# OpenEVSE_PLUS_v2_5.net
KiCad netlist of a schematic drawn in EAGLE
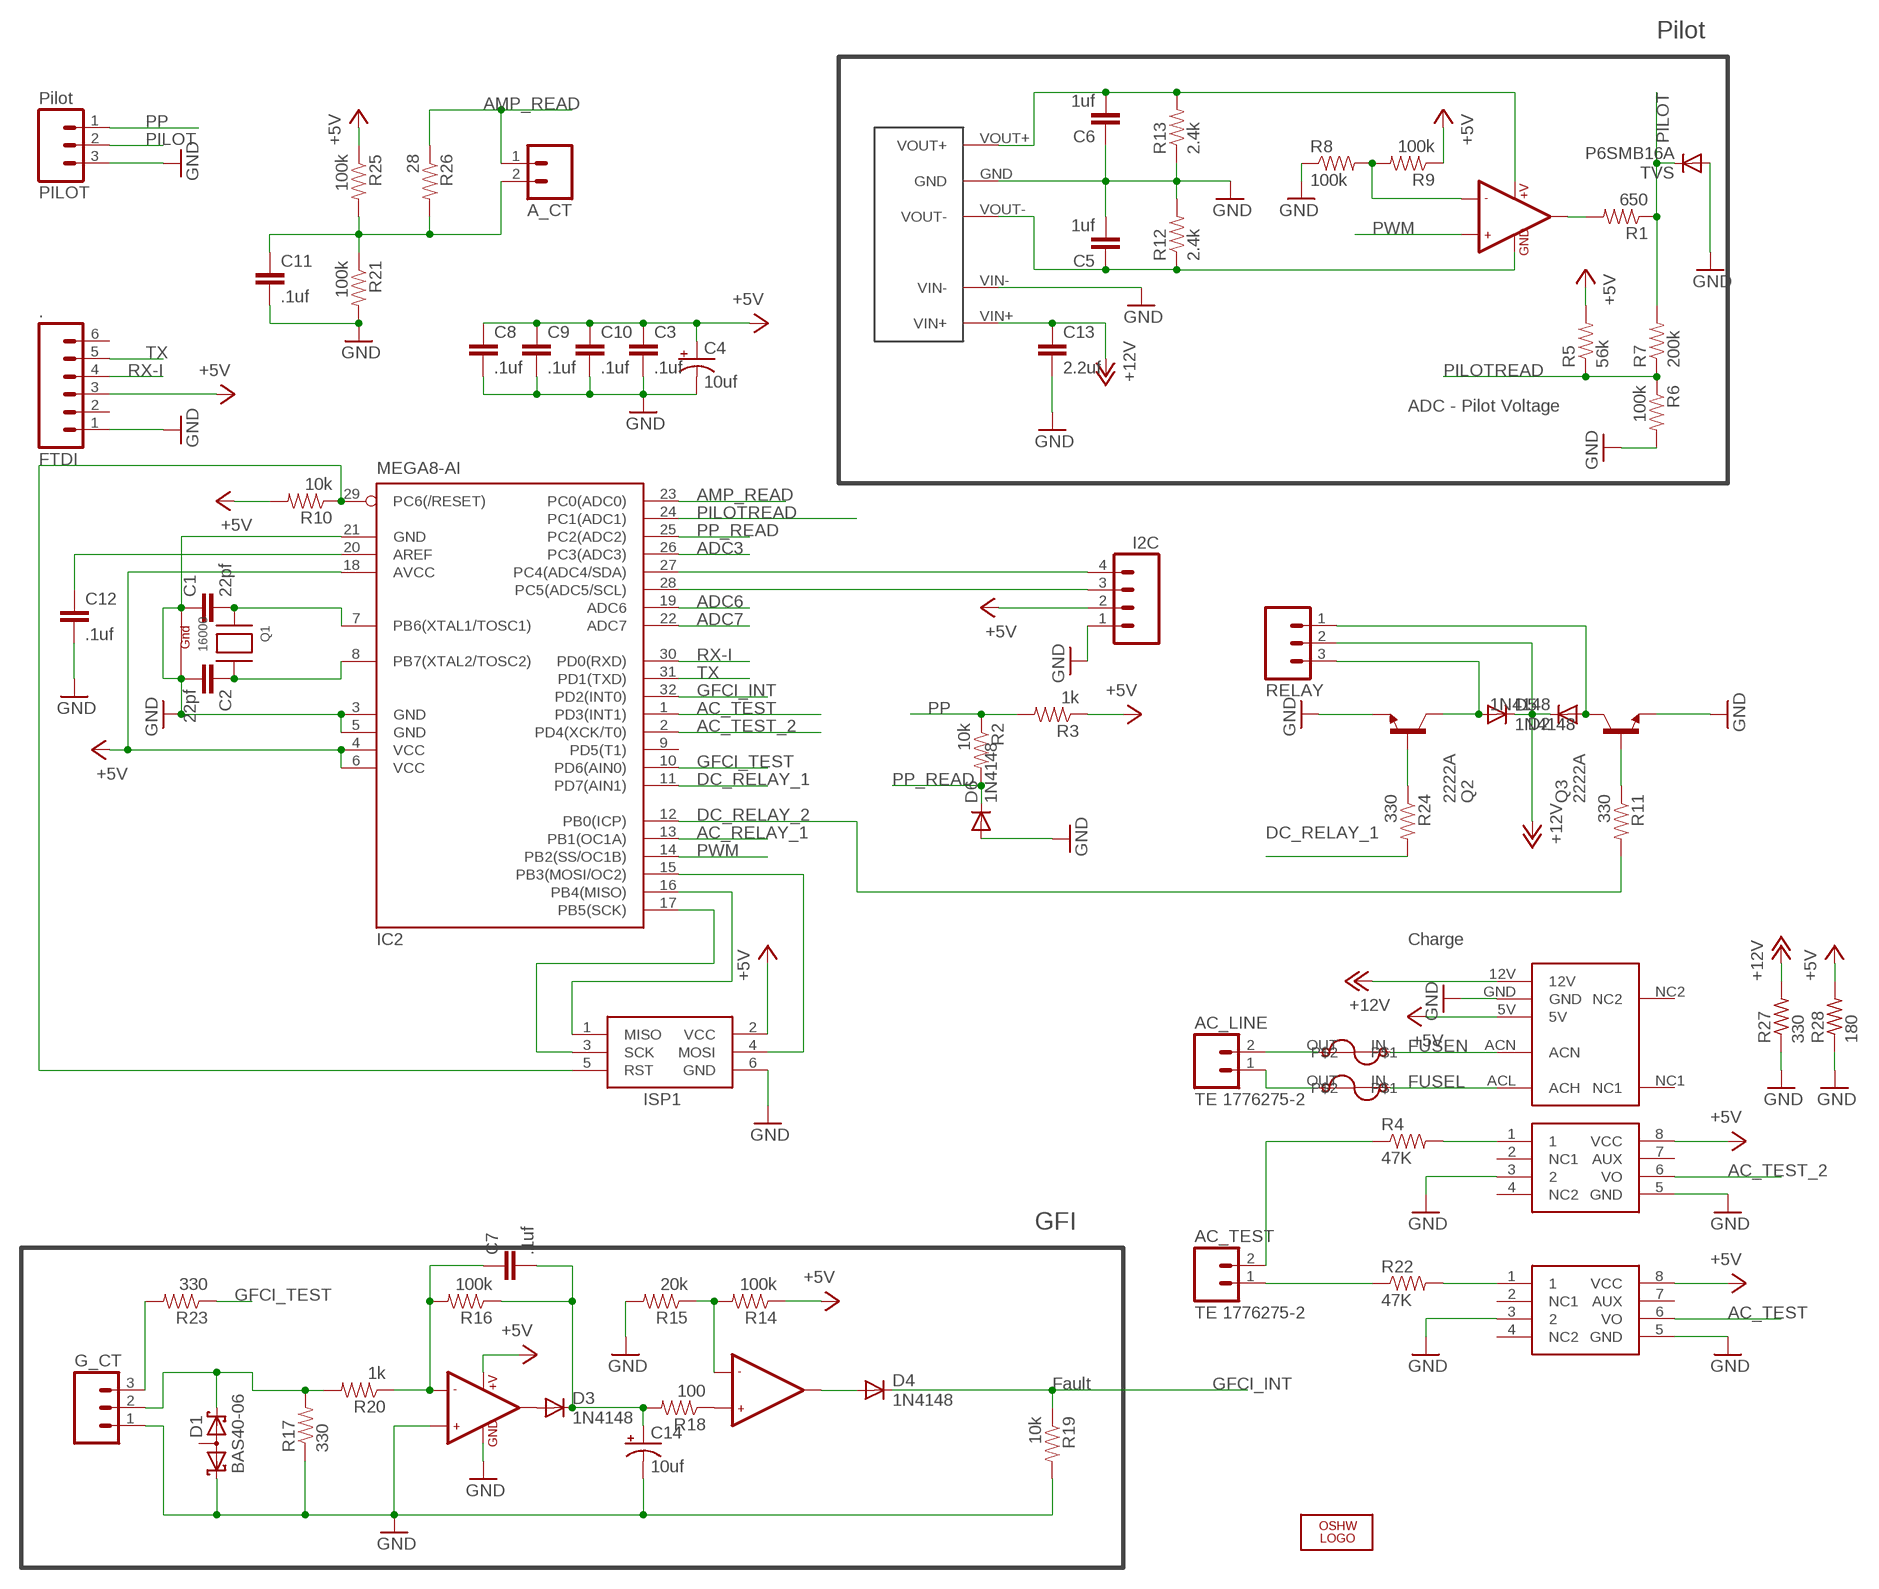
[diagram p0: schematic, sheet 1]

(export (version "E")
  (design (tool "Eeschema 10.0.6"))
  (components
    (comp (ref ".")
      (value "FTDI")
      (footprint "eagle-import:1X06_LOCK")
      (libsource (lib "eagle-import") (part "M06LOCK"))
    )
    (comp (ref "AC_LINE")
      (value "TE 1776275-2")
      (footprint "eagle-import:SCREWTERMINAL-3.5MM-2_LOCK")
      (libsource (lib "eagle-import") (part "M023.5MM_LOCK"))
    )
    (comp (ref "AC_TEST")
      (value "TE 1776275-2")
      (footprint "eagle-import:SCREWTERMINAL-3.5MM-2_LOCK")
      (libsource (lib "eagle-import") (part "M023.5MM_LOCK"))
    )
    (comp (ref "A_CT")
      (value "M02PTH")
      (footprint "eagle-import:1X02")
      (libsource (lib "eagle-import") (part "M02PTH"))
    )
    (comp (ref "C1")
      (value "22pf")
      (footprint "eagle-import:0805")
      (libsource (lib "eagle-import") (part "CAP0805"))
    )
    (comp (ref "C2")
      (value "22pf")
      (footprint "eagle-import:0805")
      (libsource (lib "eagle-import") (part "CAP0805"))
    )
    (comp (ref "C3")
      (value ".1uf")
      (footprint "eagle-import:0805")
      (libsource (lib "eagle-import") (part "CAP0805"))
    )
    (comp (ref "C4")
      (value "10uf")
      (footprint "eagle-import:EIA3216")
      (libsource (lib "eagle-import") (part "CAP_POL1206"))
    )
    (comp (ref "C5")
      (value "1uf")
      (footprint "eagle-import:0805")
      (libsource (lib "eagle-import") (part "CAP0805"))
    )
    (comp (ref "C6")
      (value "1uf")
      (footprint "eagle-import:0805")
      (libsource (lib "eagle-import") (part "CAP0805"))
    )
    (comp (ref "C7")
      (value ".1uf")
      (footprint "eagle-import:0805")
      (libsource (lib "eagle-import") (part "CAP0805"))
    )
    (comp (ref "C8")
      (value ".1uf")
      (footprint "eagle-import:0805")
      (libsource (lib "eagle-import") (part "CAP0805"))
    )
    (comp (ref "C9")
      (value ".1uf")
      (footprint "eagle-import:0805")
      (libsource (lib "eagle-import") (part "CAP0805"))
    )
    (comp (ref "C10")
      (value ".1uf")
      (footprint "eagle-import:0805")
      (libsource (lib "eagle-import") (part "CAP0805"))
    )
    (comp (ref "C11")
      (value ".1uf")
      (footprint "eagle-import:0805")
      (libsource (lib "eagle-import") (part "CAP0805"))
    )
    (comp (ref "C12")
      (value ".1uf")
      (footprint "eagle-import:0805")
      (libsource (lib "eagle-import") (part "CAP0805"))
    )
    (comp (ref "C13")
      (value "2.2uf")
      (footprint "eagle-import:0805")
      (libsource (lib "eagle-import") (part "CAP0805"))
    )
    (comp (ref "C14")
      (value "10uf")
      (footprint "eagle-import:EIA3216")
      (libsource (lib "eagle-import") (part "CAP_POL1206"))
    )
    (comp (ref "D1")
      (value "BAS40-06")
      (footprint "eagle-import:SOT23")
      (libsource (lib "eagle-import") (part "BAS40-06"))
    )
    (comp (ref "D2")
      (value "1N4148")
      (footprint "eagle-import:SOD123")
      (libsource (lib "eagle-import") (part "DIODE-SOD123"))
    )
    (comp (ref "D3")
      (value "1N4148")
      (footprint "eagle-import:SOD123")
      (libsource (lib "eagle-import") (part "DIODE-SOD123"))
    )
    (comp (ref "D4")
      (value "1N4148")
      (footprint "eagle-import:SOD123")
      (libsource (lib "eagle-import") (part "DIODE-SOD123"))
    )
    (comp (ref "D5")
      (value "1N4148")
      (footprint "eagle-import:SOD123")
      (libsource (lib "eagle-import") (part "DIODE-SOD123"))
    )
    (comp (ref "D6")
      (value "1N4148")
      (footprint "eagle-import:SOD123")
      (libsource (lib "eagle-import") (part "DIODE-SOD123"))
    )
    (comp (ref "DCDC")
      (value "D107E")
      (footprint "eagle-import:DCDC_SIP")
      (libsource (lib "eagle-import") (part "DCDC_SIP"))
    )
    (comp (ref "F1")
      (value "BEL1AFUSE")
      (footprint "eagle-import:BELFUSE1A")
      (libsource (lib "eagle-import") (part "BEL1AFUSE"))
    )
    (comp (ref "F2")
      (value "BEL1AFUSE")
      (footprint "eagle-import:BELFUSE1A")
      (libsource (lib "eagle-import") (part "BEL1AFUSE"))
    )
    (comp (ref "G_CT")
      (value "M03LOCK")
      (footprint "eagle-import:1X03_LOCK")
      (libsource (lib "eagle-import") (part "M03LOCK"))
    )
    (comp (ref "I2C")
      (value "M04LOCK")
      (footprint "eagle-import:1X04_LOCK")
      (libsource (lib "eagle-import") (part "M04LOCK"))
    )
    (comp (ref "IC1")
      (value "MID400")
      (footprint "eagle-import:DIP08")
      (libsource (lib "eagle-import") (part "MID400"))
    )
    (comp (ref "IC2")
      (value "MEGA8-AI")
      (footprint "eagle-import:TQFP32-08")
      (fields (field (name "MPN") "ATMEGA8-16AU"))
      (libsource (lib "eagle-import") (part "MEGA8-AI"))
    )
    (comp (ref "IC3")
      (value "LMV358")
      (footprint "eagle-import:SO08")
      (libsource (lib "eagle-import") (part "LMV358"))
    )
    (comp (ref "IC4")
      (value "LMV358")
      (footprint "eagle-import:SO08")
      (libsource (lib "eagle-import") (part "LMV358"))
    )
    (comp (ref "IC6")
      (value "MID400")
      (footprint "eagle-import:DIP08")
      (libsource (lib "eagle-import") (part "MID400"))
    )
    (comp (ref "ISP1")
      (value "AVRISP-6")
      (footprint "eagle-import:AVRISP")
      (libsource (lib "eagle-import") (part "AVRISP-6"))
    )
    (comp (ref "LOGO1")
      (value "OSHW_LOGO_8MILX0150-NT")
      (footprint "eagle-import:OSHW_8X150_NOTEXT")
      (libsource (lib "eagle-import") (part "OSHW_LOGO_8MILX0150-NT"))
    )
    (comp (ref "PILOT")
      (value "Pilot")
      (footprint "eagle-import:SCREWTERMINAL-3.5MM-3_LOCK.007S")
      (libsource (lib "eagle-import") (part "M03SCREW_LOCK"))
    )
    (comp (ref "Q1")
      (value "16000")
      (footprint "eagle-import:NX3225")
      (libsource (lib "eagle-import") (part "XTAL-4-3225"))
    )
    (comp (ref "Q2")
      (value "2222A")
      (footprint "eagle-import:SOT23")
      (libsource (lib "eagle-import") (part "BCX70SMD"))
    )
    (comp (ref "Q3")
      (value "2222A")
      (footprint "eagle-import:SOT23")
      (libsource (lib "eagle-import") (part "BCX70SMD"))
    )
    (comp (ref "R1")
      (value "650")
      (footprint "eagle-import:0805")
      (libsource (lib "eagle-import") (part "RESISTOR0805-RES"))
    )
    (comp (ref "R2")
      (value "10k")
      (footprint "eagle-import:0805")
      (libsource (lib "eagle-import") (part "RESISTOR0805-RES"))
    )
    (comp (ref "R3")
      (value "1k")
      (footprint "eagle-import:0805")
      (libsource (lib "eagle-import") (part "RESISTOR0805-RES"))
    )
    (comp (ref "R4")
      (value "47K")
      (footprint "eagle-import:AXIAL-0.4")
      (libsource (lib "eagle-import") (part "RESISTORPTH-1/4W"))
    )
    (comp (ref "R5")
      (value "56k")
      (footprint "eagle-import:0805")
      (libsource (lib "eagle-import") (part "RESISTOR0805-RES"))
    )
    (comp (ref "R6")
      (value "100k")
      (footprint "eagle-import:0805")
      (libsource (lib "eagle-import") (part "RESISTOR0805-RES"))
    )
    (comp (ref "R7")
      (value "200k")
      (footprint "eagle-import:0805")
      (libsource (lib "eagle-import") (part "RESISTOR0805-RES"))
    )
    (comp (ref "R8")
      (value "100k")
      (footprint "eagle-import:0805")
      (libsource (lib "eagle-import") (part "RESISTOR0805-RES"))
    )
    (comp (ref "R9")
      (value "100k")
      (footprint "eagle-import:0805")
      (libsource (lib "eagle-import") (part "RESISTOR0805-RES"))
    )
    (comp (ref "R10")
      (value "10k")
      (footprint "eagle-import:0805")
      (libsource (lib "eagle-import") (part "RESISTOR0805-RES"))
    )
    (comp (ref "R11")
      (value "330")
      (footprint "eagle-import:0805")
      (libsource (lib "eagle-import") (part "RESISTOR0805-RES"))
    )
    (comp (ref "R12")
      (value "2.4k")
      (footprint "eagle-import:0805")
      (libsource (lib "eagle-import") (part "RESISTOR0805-RES"))
    )
    (comp (ref "R13")
      (value "2.4k")
      (footprint "eagle-import:0805")
      (libsource (lib "eagle-import") (part "RESISTOR0805-RES"))
    )
    (comp (ref "R14")
      (value "100k")
      (footprint "eagle-import:0805")
      (libsource (lib "eagle-import") (part "RESISTOR0805-RES"))
    )
    (comp (ref "R15")
      (value "20k")
      (footprint "eagle-import:0805")
      (libsource (lib "eagle-import") (part "RESISTOR0805-RES"))
    )
    (comp (ref "R16")
      (value "100k")
      (footprint "eagle-import:0805")
      (libsource (lib "eagle-import") (part "RESISTOR0805-RES"))
    )
    (comp (ref "R17")
      (value "330")
      (footprint "eagle-import:0805")
      (libsource (lib "eagle-import") (part "RESISTOR0805-RES"))
    )
    (comp (ref "R18")
      (value "100")
      (footprint "eagle-import:0805")
      (libsource (lib "eagle-import") (part "RESISTOR0805-RES"))
    )
    (comp (ref "R19")
      (value "10k")
      (footprint "eagle-import:0805")
      (libsource (lib "eagle-import") (part "RESISTOR0805-RES"))
    )
    (comp (ref "R20")
      (value "1k")
      (footprint "eagle-import:0805")
      (libsource (lib "eagle-import") (part "RESISTOR0805-RES"))
    )
    (comp (ref "R21")
      (value "100k")
      (footprint "eagle-import:0805")
      (libsource (lib "eagle-import") (part "RESISTOR0805-RES"))
    )
    (comp (ref "R22")
      (value "47K")
      (footprint "eagle-import:AXIAL-0.4")
      (libsource (lib "eagle-import") (part "RESISTORPTH-1/4W"))
    )
    (comp (ref "R23")
      (value "330")
      (footprint "eagle-import:0805")
      (libsource (lib "eagle-import") (part "RESISTOR0805-RES"))
    )
    (comp (ref "R24")
      (value "330")
      (footprint "eagle-import:0805")
      (libsource (lib "eagle-import") (part "RESISTOR0805-RES"))
    )
    (comp (ref "R25")
      (value "100k")
      (footprint "eagle-import:0805")
      (libsource (lib "eagle-import") (part "RESISTOR0805-RES"))
    )
    (comp (ref "R26")
      (value "28")
      (footprint "eagle-import:0805")
      (libsource (lib "eagle-import") (part "RESISTOR0805-RES"))
    )
    (comp (ref "R27")
      (value "330")
      (footprint "eagle-import:R1206")
      (libsource (lib "eagle-import") (part "R-US_R1206"))
    )
    (comp (ref "R28")
      (value "180")
      (footprint "eagle-import:R1206")
      (libsource (lib "eagle-import") (part "R-US_R1206"))
    )
    (comp (ref "RELAY")
      (value "M03SCREW_LOCK")
      (footprint "eagle-import:SCREWTERMINAL-3.5MM-3_LOCK.007S")
      (libsource (lib "eagle-import") (part "M03SCREW_LOCK"))
    )
    (comp (ref "TVS")
      (value "P6SMB16A")
      (footprint "eagle-import:SMB")
      (libsource (lib "eagle-import") (part "DIODE-SMB"))
    )
    (comp (ref "U$1")
      (value "MPM-04E-1205")
      (footprint "eagle-import:MPM-04E-1205")
      (libsource (lib "eagle-import") (part "MPM-04E-1205"))
    )
  )
  (nets
    (net (code "1") (name "+5V") (class "Default")
      (node (ref ".") (pin "3") (pinfunction "3_3") (pintype "passive"))
      (node (ref "C10") (pin "1") (pinfunction "1_1") (pintype "passive"))
      (node (ref "C3") (pin "1") (pinfunction "1_1") (pintype "passive"))
      (node (ref "C4") (pin "A") (pinfunction "+_A") (pintype "passive"))
      (node (ref "C8") (pin "1") (pinfunction "1_1") (pintype "passive"))
      (node (ref "C9") (pin "1") (pinfunction "1_1") (pintype "passive"))
      (node (ref "I2C") (pin "2") (pinfunction "2_2") (pintype "passive"))
      (node (ref "IC1") (pin "8") (pinfunction "VCC_8") (pintype "bidirectional"))
      (node (ref "IC2") (pin "18") (pinfunction "AVCC_18") (pintype "power_in"))
      (node (ref "IC2") (pin "4") (pinfunction "VCC_4") (pintype "power_in"))
      (node (ref "IC2") (pin "6") (pinfunction "VCC_6") (pintype "power_in"))
      (node (ref "IC3") (pin "8") (pinfunction "+V_8") (pintype "power_in"))
      (node (ref "IC6") (pin "8") (pinfunction "VCC_8") (pintype "bidirectional"))
      (node (ref "ISP1") (pin "2") (pinfunction "VCC_2") (pintype "power_in"))
      (node (ref "R10") (pin "2") (pinfunction "2_2") (pintype "passive"))
      (node (ref "R14") (pin "1") (pinfunction "1_1") (pintype "passive"))
      (node (ref "R25") (pin "1") (pinfunction "1_1") (pintype "passive"))
      (node (ref "R28") (pin "2") (pinfunction "2_2") (pintype "passive"))
      (node (ref "R3") (pin "1") (pinfunction "1_1") (pintype "passive"))
      (node (ref "R5") (pin "2") (pinfunction "2_2") (pintype "passive"))
      (node (ref "R9") (pin "1") (pinfunction "1_1") (pintype "passive"))
      (node (ref "U$1") (pin "5V") (pinfunction "5V_5V") (pintype "bidirectional"))
    )
    (net (code "2") (name "+12V") (class "Default")
      (node (ref "C13") (pin "1") (pinfunction "1_1") (pintype "passive"))
      (node (ref "D2") (pin "C") (pinfunction "C_C") (pintype "passive"))
      (node (ref "D5") (pin "C") (pinfunction "C_C") (pintype "passive"))
      (node (ref "DCDC") (pin "VIN+") (pinfunction "VIN+_VIN+") (pintype "bidirectional"))
      (node (ref "R27") (pin "2") (pinfunction "2_2") (pintype "passive"))
      (node (ref "RELAY") (pin "2") (pinfunction "2_2") (pintype "passive"))
      (node (ref "U$1") (pin "12V") (pinfunction "12V_12V") (pintype "bidirectional"))
    )
    (net (code "3") (name "/AC_RELAY_1") (class "Default")
      (node (ref "IC2") (pin "13") (pinfunction "PB1(OC1A)_13") (pintype "bidirectional"))
    )
    (net (code "4") (name "/AC_TEST") (class "Default")
      (node (ref "IC2") (pin "1") (pinfunction "PD3(INT1)_1") (pintype "bidirectional"))
      (node (ref "IC6") (pin "6") (pinfunction "VO_6") (pintype "bidirectional"))
    )
    (net (code "5") (name "/AC_TEST_2") (class "Default")
      (node (ref "IC1") (pin "6") (pinfunction "VO_6") (pintype "bidirectional"))
      (node (ref "IC2") (pin "2") (pinfunction "PD4(XCK/T0)_2") (pintype "bidirectional"))
    )
    (net (code "6") (name "/ADC3") (class "Default")
      (node (ref "IC2") (pin "26") (pinfunction "PC3(ADC3)_26") (pintype "bidirectional"))
    )
    (net (code "7") (name "/ADC6") (class "Default")
      (node (ref "IC2") (pin "19") (pinfunction "ADC6_19") (pintype "bidirectional"))
    )
    (net (code "8") (name "/ADC7") (class "Default")
      (node (ref "IC2") (pin "22") (pinfunction "ADC7_22") (pintype "bidirectional"))
    )
    (net (code "9") (name "/AMP_READ") (class "Default")
      (node (ref "A_CT") (pin "1") (pinfunction "1_1") (pintype "passive"))
      (node (ref "IC2") (pin "23") (pinfunction "PC0(ADC0)_23") (pintype "bidirectional"))
      (node (ref "R26") (pin "1") (pinfunction "1_1") (pintype "passive"))
    )
    (net (code "10") (name "/DC_RELAY_1") (class "Default")
      (node (ref "IC2") (pin "11") (pinfunction "PD7(AIN1)_11") (pintype "bidirectional"))
      (node (ref "R24") (pin "2") (pinfunction "2_2") (pintype "passive"))
    )
    (net (code "11") (name "/DC_RELAY_2") (class "Default")
      (node (ref "IC2") (pin "12") (pinfunction "PB0(ICP)_12") (pintype "bidirectional"))
      (node (ref "R11") (pin "2") (pinfunction "2_2") (pintype "passive"))
    )
    (net (code "12") (name "/FUSEL") (class "Default")
      (node (ref "F2") (pin "IN") (pinfunction "P$2_IN") (pintype "bidirectional"))
      (node (ref "U$1") (pin "ACL") (pinfunction "ACH_ACL") (pintype "bidirectional"))
    )
    (net (code "13") (name "/FUSEN") (class "Default")
      (node (ref "F1") (pin "IN") (pinfunction "P$2_IN") (pintype "bidirectional"))
      (node (ref "U$1") (pin "ACN") (pinfunction "ACN_ACN") (pintype "bidirectional"))
    )
    (net (code "14") (name "/GFCI_INT") (class "Default")
      (node (ref "D4") (pin "C") (pinfunction "C_C") (pintype "passive"))
      (node (ref "IC2") (pin "32") (pinfunction "PD2(INT0)_32") (pintype "bidirectional"))
      (node (ref "R19") (pin "1") (pinfunction "1_1") (pintype "passive"))
    )
    (net (code "15") (name "/GFCI_TEST") (class "Default")
      (node (ref "IC2") (pin "10") (pinfunction "PD6(AIN0)_10") (pintype "bidirectional"))
      (node (ref "R23") (pin "1") (pinfunction "1_1") (pintype "passive"))
    )
    (net (code "16") (name "/PILOT") (class "Default")
      (node (ref "PILOT") (pin "2") (pinfunction "2_2") (pintype "passive"))
      (node (ref "R1") (pin "1") (pinfunction "1_1") (pintype "passive"))
      (node (ref "R7") (pin "2") (pinfunction "2_2") (pintype "passive"))
      (node (ref "TVS") (pin "C") (pinfunction "C_C") (pintype "passive"))
    )
    (net (code "17") (name "/PILOTREAD") (class "Default")
      (node (ref "IC2") (pin "24") (pinfunction "PC1(ADC1)_24") (pintype "bidirectional"))
      (node (ref "R5") (pin "1") (pinfunction "1_1") (pintype "passive"))
      (node (ref "R6") (pin "1") (pinfunction "1_1") (pintype "passive"))
      (node (ref "R7") (pin "1") (pinfunction "1_1") (pintype "passive"))
    )
    (net (code "18") (name "/PP") (class "Default")
      (node (ref "PILOT") (pin "1") (pinfunction "1_1") (pintype "passive"))
      (node (ref "R2") (pin "1") (pinfunction "1_1") (pintype "passive"))
      (node (ref "R3") (pin "2") (pinfunction "2_2") (pintype "passive"))
    )
    (net (code "19") (name "/PP_READ") (class "Default")
      (node (ref "D6") (pin "C") (pinfunction "C_C") (pintype "passive"))
      (node (ref "IC2") (pin "25") (pinfunction "PC2(ADC2)_25") (pintype "bidirectional"))
      (node (ref "R2") (pin "2") (pinfunction "2_2") (pintype "passive"))
    )
    (net (code "20") (name "/PWM") (class "Default")
      (node (ref "IC2") (pin "14") (pinfunction "PB2(SS/OC1B)_14") (pintype "bidirectional"))
      (node (ref "IC4") (pin "3") (pinfunction "+IN1_3") (pintype "input"))
    )
    (net (code "21") (name "/RX-I") (class "Default")
      (node (ref ".") (pin "4") (pinfunction "4_4") (pintype "passive"))
      (node (ref "IC2") (pin "30") (pinfunction "PD0(RXD)_30") (pintype "bidirectional"))
    )
    (net (code "22") (name "/TX") (class "Default")
      (node (ref ".") (pin "5") (pinfunction "5_5") (pintype "passive"))
      (node (ref "IC2") (pin "31") (pinfunction "PD1(TXD)_31") (pintype "bidirectional"))
    )
    (net (code "23") (name "GND") (class "Default")
      (node (ref ".") (pin "1") (pinfunction "1_1") (pintype "passive"))
      (node (ref "C1") (pin "1") (pinfunction "1_1") (pintype "passive"))
      (node (ref "C10") (pin "2") (pinfunction "2_2") (pintype "passive"))
      (node (ref "C11") (pin "2") (pinfunction "2_2") (pintype "passive"))
      (node (ref "C12") (pin "2") (pinfunction "2_2") (pintype "passive"))
      (node (ref "C13") (pin "2") (pinfunction "2_2") (pintype "passive"))
      (node (ref "C14") (pin "C") (pinfunction "-_C") (pintype "passive"))
      (node (ref "C2") (pin "2") (pinfunction "2_2") (pintype "passive"))
      (node (ref "C3") (pin "2") (pinfunction "2_2") (pintype "passive"))
      (node (ref "C4") (pin "C") (pinfunction "-_C") (pintype "passive"))
      (node (ref "C5") (pin "2") (pinfunction "2_2") (pintype "passive"))
      (node (ref "C6") (pin "1") (pinfunction "1_1") (pintype "passive"))
      (node (ref "C8") (pin "2") (pinfunction "2_2") (pintype "passive"))
      (node (ref "C9") (pin "2") (pinfunction "2_2") (pintype "passive"))
      (node (ref "D1") (pin "1") (pinfunction "K1_1") (pintype "passive"))
      (node (ref "D6") (pin "A") (pinfunction "A_A") (pintype "passive"))
      (node (ref "DCDC") (pin "GND") (pinfunction "GND_GND") (pintype "bidirectional"))
      (node (ref "DCDC") (pin "VIN-") (pinfunction "VIN-_VIN-") (pintype "bidirectional"))
      (node (ref "G_CT") (pin "1") (pinfunction "1_1") (pintype "passive"))
      (node (ref "I2C") (pin "1") (pinfunction "1_1") (pintype "passive"))
      (node (ref "IC1") (pin "3") (pinfunction "2_3") (pintype "bidirectional"))
      (node (ref "IC1") (pin "5") (pinfunction "GND_5") (pintype "bidirectional"))
      (node (ref "IC2") (pin "21") (pinfunction "GND_21") (pintype "power_in"))
      (node (ref "IC2") (pin "3") (pinfunction "GND_3") (pintype "power_in"))
      (node (ref "IC2") (pin "5") (pinfunction "GND_5") (pintype "power_in"))
      (node (ref "IC3") (pin "3") (pinfunction "+IN1_3") (pintype "input"))
      (node (ref "IC3") (pin "4") (pinfunction "GND_4") (pintype "power_in"))
      (node (ref "IC6") (pin "3") (pinfunction "2_3") (pintype "bidirectional"))
      (node (ref "IC6") (pin "5") (pinfunction "GND_5") (pintype "bidirectional"))
      (node (ref "ISP1") (pin "6") (pinfunction "GND_6") (pintype "power_in"))
      (node (ref "PILOT") (pin "3") (pinfunction "3_3") (pintype "passive"))
      (node (ref "Q1") (pin "1") (pinfunction "G1_1") (pintype "power_in"))
      (node (ref "Q1") (pin "3") (pinfunction "G2_3") (pintype "power_in"))
      (node (ref "Q2") (pin "2") (pinfunction "E_2") (pintype "passive"))
      (node (ref "Q3") (pin "2") (pinfunction "E_2") (pintype "passive"))
      (node (ref "R12") (pin "2") (pinfunction "2_2") (pintype "passive"))
      (node (ref "R13") (pin "1") (pinfunction "1_1") (pintype "passive"))
      (node (ref "R15") (pin "2") (pinfunction "2_2") (pintype "passive"))
      (node (ref "R17") (pin "1") (pinfunction "1_1") (pintype "passive"))
      (node (ref "R19") (pin "2") (pinfunction "2_2") (pintype "passive"))
      (node (ref "R21") (pin "2") (pinfunction "2_2") (pintype "passive"))
      (node (ref "R27") (pin "1") (pinfunction "1_1") (pintype "passive"))
      (node (ref "R28") (pin "1") (pinfunction "1_1") (pintype "passive"))
      (node (ref "R6") (pin "2") (pinfunction "2_2") (pintype "passive"))
      (node (ref "R8") (pin "1") (pinfunction "1_1") (pintype "passive"))
      (node (ref "TVS") (pin "A") (pinfunction "A_A") (pintype "passive"))
      (node (ref "U$1") (pin "GND") (pinfunction "GND_GND") (pintype "bidirectional"))
    )
    (net (code "24") (name "Net-(A_CT-Pad2)") (class "Default")
      (node (ref "A_CT") (pin "2") (pinfunction "2_2") (pintype "passive"))
      (node (ref "C11") (pin "1") (pinfunction "1_1") (pintype "passive"))
      (node (ref "R21") (pin "1") (pinfunction "1_1") (pintype "passive"))
      (node (ref "R25") (pin "2") (pinfunction "2_2") (pintype "passive"))
      (node (ref "R26") (pin "2") (pinfunction "2_2") (pintype "passive"))
    )
    (net (code "25") (name "Net-(C14-+)") (class "Default")
      (node (ref "C14") (pin "A") (pinfunction "+_A") (pintype "passive"))
      (node (ref "C7") (pin "2") (pinfunction "2_2") (pintype "passive"))
      (node (ref "D3") (pin "C") (pinfunction "C_C") (pintype "passive"))
      (node (ref "R16") (pin "1") (pinfunction "1_1") (pintype "passive"))
      (node (ref "R18") (pin "2") (pinfunction "2_2") (pintype "passive"))
    )
    (net (code "26") (name "Net-(D1-K2)") (class "Default")
      (node (ref "D1") (pin "2") (pinfunction "K2_2") (pintype "passive"))
      (node (ref "G_CT") (pin "2") (pinfunction "2_2") (pintype "passive"))
      (node (ref "R17") (pin "2") (pinfunction "2_2") (pintype "passive"))
      (node (ref "R20") (pin "2") (pinfunction "2_2") (pintype "passive"))
    )
    (net (code "27") (name "Net-(F1-P$1)") (class "Default")
      (node (ref "AC_LINE") (pin "2") (pinfunction "2_2") (pintype "passive"))
      (node (ref "F1") (pin "OUT") (pinfunction "P$1_OUT") (pintype "bidirectional"))
    )
    (net (code "28") (name "Net-(F2-P$1)") (class "Default")
      (node (ref "AC_LINE") (pin "1") (pinfunction "1_1") (pintype "passive"))
      (node (ref "F2") (pin "OUT") (pinfunction "P$1_OUT") (pintype "bidirectional"))
    )
    (net (code "29") (name "Net-(G_CT-Pad3)") (class "Default")
      (node (ref "G_CT") (pin "3") (pinfunction "3_3") (pintype "passive"))
      (node (ref "R23") (pin "2") (pinfunction "2_2") (pintype "passive"))
    )
    (net (code "30") (name "Net-(IC2-AREF)") (class "Default")
      (node (ref "C12") (pin "1") (pinfunction "1_1") (pintype "passive"))
      (node (ref "IC2") (pin "20") (pinfunction "AREF_20") (pintype "passive"))
    )
    (net (code "31") (name "Net-(IC2-PB3(MOSI{slash}OC2))") (class "Default")
      (node (ref "IC2") (pin "15") (pinfunction "PB3(MOSI/OC2)_15") (pintype "bidirectional"))
      (node (ref "ISP1") (pin "4") (pinfunction "MOSI_4") (pintype "output"))
    )
    (net (code "32") (name "Net-(IC2-PB4(MISO))") (class "Default")
      (node (ref "IC2") (pin "16") (pinfunction "PB4(MISO)_16") (pintype "bidirectional"))
      (node (ref "ISP1") (pin "1") (pinfunction "MISO_1") (pintype "input"))
    )
    (net (code "33") (name "Net-(IC2-PB5(SCK))") (class "Default")
      (node (ref "IC2") (pin "17") (pinfunction "PB5(SCK)_17") (pintype "bidirectional"))
      (node (ref "ISP1") (pin "3") (pinfunction "SCK_3") (pintype "output"))
    )
    (net (code "34") (name "Net-(IC2-PB6(XTAL1{slash}TOSC1))") (class "Default")
      (node (ref "C1") (pin "2") (pinfunction "2_2") (pintype "passive"))
      (node (ref "IC2") (pin "7") (pinfunction "PB6(XTAL1/TOSC1)_7") (pintype "bidirectional"))
      (node (ref "Q1") (pin "2") (pinfunction "X1_2") (pintype "bidirectional"))
    )
    (net (code "35") (name "Net-(IC2-PB7(XTAL2{slash}TOSC2))") (class "Default")
      (node (ref "C2") (pin "1") (pinfunction "1_1") (pintype "passive"))
      (node (ref "IC2") (pin "8") (pinfunction "PB7(XTAL2/TOSC2)_8") (pintype "bidirectional"))
      (node (ref "Q1") (pin "4") (pinfunction "X2_4") (pintype "bidirectional"))
    )
    (net (code "36") (name "Net-(IC2-PC4(ADC4{slash}SDA))") (class "Default")
      (node (ref "I2C") (pin "4") (pinfunction "4_4") (pintype "passive"))
      (node (ref "IC2") (pin "27") (pinfunction "PC4(ADC4/SDA)_27") (pintype "bidirectional"))
    )
    (net (code "37") (name "Net-(IC2-PC5(ADC5{slash}SCL))") (class "Default")
      (node (ref "I2C") (pin "3") (pinfunction "3_3") (pintype "passive"))
      (node (ref "IC2") (pin "28") (pinfunction "PC5(ADC5/SCL)_28") (pintype "bidirectional"))
    )
    (net (code "38") (name "Net-(IC2-PC6({slash}RESET))") (class "Default")
      (node (ref "IC2") (pin "29") (pinfunction "PC6(/RESET)_29") (pintype "bidirectional"))
      (node (ref "ISP1") (pin "5") (pinfunction "RST_5") (pintype "output"))
      (node (ref "R10") (pin "1") (pinfunction "1_1") (pintype "passive"))
    )
    (net (code "39") (name "Net-(IC3A--IN1)") (class "Default")
      (node (ref "C7") (pin "1") (pinfunction "1_1") (pintype "passive"))
      (node (ref "IC3") (pin "2") (pinfunction "-IN1_2") (pintype "input"))
      (node (ref "R16") (pin "2") (pinfunction "2_2") (pintype "passive"))
      (node (ref "R20") (pin "1") (pinfunction "1_1") (pintype "passive"))
    )
    (net (code "40") (name "Net-(IC3A-OUT1)") (class "Default")
      (node (ref "D3") (pin "A") (pinfunction "A_A") (pintype "passive"))
      (node (ref "IC3") (pin "1") (pinfunction "OUT1_1") (pintype "output"))
    )
    (net (code "41") (name "Net-(IC3B-+IN2)") (class "Default")
      (node (ref "IC3") (pin "5") (pinfunction "+IN2_5") (pintype "input"))
      (node (ref "R18") (pin "1") (pinfunction "1_1") (pintype "passive"))
    )
    (net (code "42") (name "Net-(IC3B--IN2)") (class "Default")
      (node (ref "IC3") (pin "6") (pinfunction "-IN2_6") (pintype "input"))
      (node (ref "R14") (pin "2") (pinfunction "2_2") (pintype "passive"))
      (node (ref "R15") (pin "1") (pinfunction "1_1") (pintype "passive"))
    )
    (net (code "43") (name "Net-(IC3B-OUT2)") (class "Default")
      (node (ref "D4") (pin "A") (pinfunction "A_A") (pintype "passive"))
      (node (ref "IC3") (pin "7") (pinfunction "OUT2_7") (pintype "output"))
    )
    (net (code "44") (name "Net-(IC4A-+V)") (class "Default")
      (node (ref "C6") (pin "2") (pinfunction "2_2") (pintype "passive"))
      (node (ref "DCDC") (pin "VOUT+") (pinfunction "VOUT+_VOUT+") (pintype "bidirectional"))
      (node (ref "IC4") (pin "8") (pinfunction "+V_8") (pintype "power_in"))
      (node (ref "R13") (pin "2") (pinfunction "2_2") (pintype "passive"))
    )
    (net (code "45") (name "Net-(IC4A--IN1)") (class "Default")
      (node (ref "IC4") (pin "2") (pinfunction "-IN1_2") (pintype "input"))
      (node (ref "R8") (pin "2") (pinfunction "2_2") (pintype "passive"))
      (node (ref "R9") (pin "2") (pinfunction "2_2") (pintype "passive"))
    )
    (net (code "46") (name "Net-(IC4A-GND)") (class "Default")
      (node (ref "C5") (pin "1") (pinfunction "1_1") (pintype "passive"))
      (node (ref "DCDC") (pin "VOUT-") (pinfunction "VOUT-_VOUT-") (pintype "bidirectional"))
      (node (ref "IC4") (pin "4") (pinfunction "GND_4") (pintype "power_in"))
      (node (ref "R12") (pin "1") (pinfunction "1_1") (pintype "passive"))
    )
    (net (code "47") (name "Net-(IC4A-OUT1)") (class "Default")
      (node (ref "IC4") (pin "1") (pinfunction "OUT1_1") (pintype "output"))
      (node (ref "R1") (pin "2") (pinfunction "2_2") (pintype "passive"))
    )
    (net (code "48") (name "Net-(Q2-B)") (class "Default")
      (node (ref "Q2") (pin "1") (pinfunction "B_1") (pintype "passive"))
      (node (ref "R24") (pin "1") (pinfunction "1_1") (pintype "passive"))
    )
    (net (code "49") (name "Net-(Q2-C)") (class "Default")
      (node (ref "D5") (pin "A") (pinfunction "A_A") (pintype "passive"))
      (node (ref "Q2") (pin "3") (pinfunction "C_3") (pintype "passive"))
      (node (ref "RELAY") (pin "3") (pinfunction "3_3") (pintype "passive"))
    )
    (net (code "50") (name "Net-(Q3-B)") (class "Default")
      (node (ref "Q3") (pin "1") (pinfunction "B_1") (pintype "passive"))
      (node (ref "R11") (pin "1") (pinfunction "1_1") (pintype "passive"))
    )
    (net (code "51") (name "Net-(Q3-C)") (class "Default")
      (node (ref "D2") (pin "A") (pinfunction "A_A") (pintype "passive"))
      (node (ref "Q3") (pin "3") (pinfunction "C_3") (pintype "passive"))
      (node (ref "RELAY") (pin "1") (pinfunction "1_1") (pintype "passive"))
    )
    (net (code "52") (name "Net-(R4-1)") (class "Default")
      (node (ref "AC_TEST") (pin "2") (pinfunction "2_2") (pintype "passive"))
      (node (ref "R4") (pin "P$1") (pinfunction "1_P$1") (pintype "passive"))
    )
    (net (code "53") (name "Net-(R4-2)") (class "Default")
      (node (ref "IC1") (pin "1") (pinfunction "1_1") (pintype "bidirectional"))
      (node (ref "R4") (pin "P$2") (pinfunction "2_P$2") (pintype "passive"))
    )
    (net (code "54") (name "Net-(R22-1)") (class "Default")
      (node (ref "AC_TEST") (pin "1") (pinfunction "1_1") (pintype "passive"))
      (node (ref "R22") (pin "P$1") (pinfunction "1_P$1") (pintype "passive"))
    )
    (net (code "55") (name "Net-(R22-2)") (class "Default")
      (node (ref "IC6") (pin "1") (pinfunction "1_1") (pintype "bidirectional"))
      (node (ref "R22") (pin "P$2") (pinfunction "2_P$2") (pintype "passive"))
    )
    (net (code "56") (name "unconnected-(.-Pad2)") (class "Default")
      (node (ref ".") (pin "2") (pinfunction "2_2") (pintype "passive"))
    )
    (net (code "57") (name "unconnected-(.-Pad6)") (class "Default")
      (node (ref ".") (pin "6") (pinfunction "6_6") (pintype "passive"))
    )
    (net (code "58") (name "unconnected-(D1-AA-Pad3)") (class "Default")
      (node (ref "D1") (pin "3") (pinfunction "AA_3") (pintype "passive"))
    )
    (net (code "59") (name "unconnected-(IC1-AUX-Pad7)") (class "Default")
      (node (ref "IC1") (pin "7") (pinfunction "AUX_7") (pintype "bidirectional"))
    )
    (net (code "60") (name "unconnected-(IC1-NC1-Pad2)") (class "Default")
      (node (ref "IC1") (pin "2") (pinfunction "NC1_2") (pintype "bidirectional"))
    )
    (net (code "61") (name "unconnected-(IC1-NC2-Pad4)") (class "Default")
      (node (ref "IC1") (pin "4") (pinfunction "NC2_4") (pintype "bidirectional"))
    )
    (net (code "62") (name "unconnected-(IC2-PD5(T1)-Pad9)") (class "Default")
      (node (ref "IC2") (pin "9") (pinfunction "PD5(T1)_9") (pintype "bidirectional"))
    )
    (net (code "63") (name "unconnected-(IC6-AUX-Pad7)") (class "Default")
      (node (ref "IC6") (pin "7") (pinfunction "AUX_7") (pintype "bidirectional"))
    )
    (net (code "64") (name "unconnected-(IC6-NC1-Pad2)") (class "Default")
      (node (ref "IC6") (pin "2") (pinfunction "NC1_2") (pintype "bidirectional"))
    )
    (net (code "65") (name "unconnected-(IC6-NC2-Pad4)") (class "Default")
      (node (ref "IC6") (pin "4") (pinfunction "NC2_4") (pintype "bidirectional"))
    )
    (net (code "66") (name "unconnected-(U$1-PadNC1)") (class "Default")
      (node (ref "U$1") (pin "NC1") (pinfunction "NC1_NC1") (pintype "bidirectional"))
    )
    (net (code "67") (name "unconnected-(U$1-PadNC2)") (class "Default")
      (node (ref "U$1") (pin "NC2") (pinfunction "NC2_NC2") (pintype "bidirectional"))
    )
  )
)
